# LEDProject.net
KiCad netlist of a schematic drawn in Altium Designer
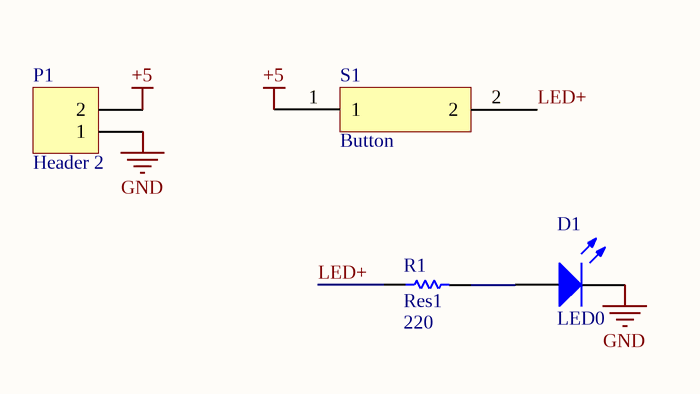
[diagram p0: LEDProject.SchDoc]

(export (version "E")
  (design (tool "Eeschema 10.0.6"))
  (components
    (comp (ref "D1")
      (value "LED0")
      (footprint "LED-0")
      (description "Typical INFRARED GaAs LED")
      (fields (field (name "PUBLISHER") "Altium Limited"))
      (libsource (lib "Miscellaneous Devices") (part "LED0"))
    )
    (comp (ref "P1")
      (value "Header 2")
      (footprint "HDR1X2")
      (description "Header, 2-Pin")
      (fields (field (name "PUBLISHER") "Altium Limited"))
      (libsource (lib "Miscellaneous Connectors") (part "Header 2"))
    )
    (comp (ref "R1")
      (value "Res1")
      (footprint "C0805")
      (description "Resistor")
      (fields (field (name "ALTIUM_VALUE") "220") (field (name "PUBLISHER") "Altium Limited"))
      (libsource (lib "Miscellaneous Devices") (part "Res1"))
    )
    (comp (ref "S1") (value "Button") (footprint "c0805") (libsource (lib "LEDProject") (part "Button")))
  )
  (nets
    (net (code "1") (name "+5") (class "Default")
      (node (ref "P1") (pin "2") (pinfunction "2_2") (pintype "passive"))
      (node (ref "S1") (pin "1") (pinfunction "1_1") (pintype "passive"))
    )
    (net (code "2") (name "/LED+") (class "Default")
      (node (ref "R1") (pin "1") (pinfunction "1_1") (pintype "passive"))
      (node (ref "S1") (pin "2") (pinfunction "2_2") (pintype "passive"))
    )
    (net (code "3") (name "GND") (class "Default")
      (node (ref "D1") (pin "2") (pinfunction "K_2") (pintype "passive"))
      (node (ref "P1") (pin "1") (pinfunction "1_1") (pintype "passive"))
    )
    (net (code "4") (name "Net-(D1-A)") (class "Default")
      (node (ref "D1") (pin "1") (pinfunction "A_1") (pintype "passive"))
      (node (ref "R1") (pin "2") (pinfunction "2_2") (pintype "passive"))
    )
  )
)
